# Key-Matrix.net
KiCad netlist of a schematic drawn in Altium Designer
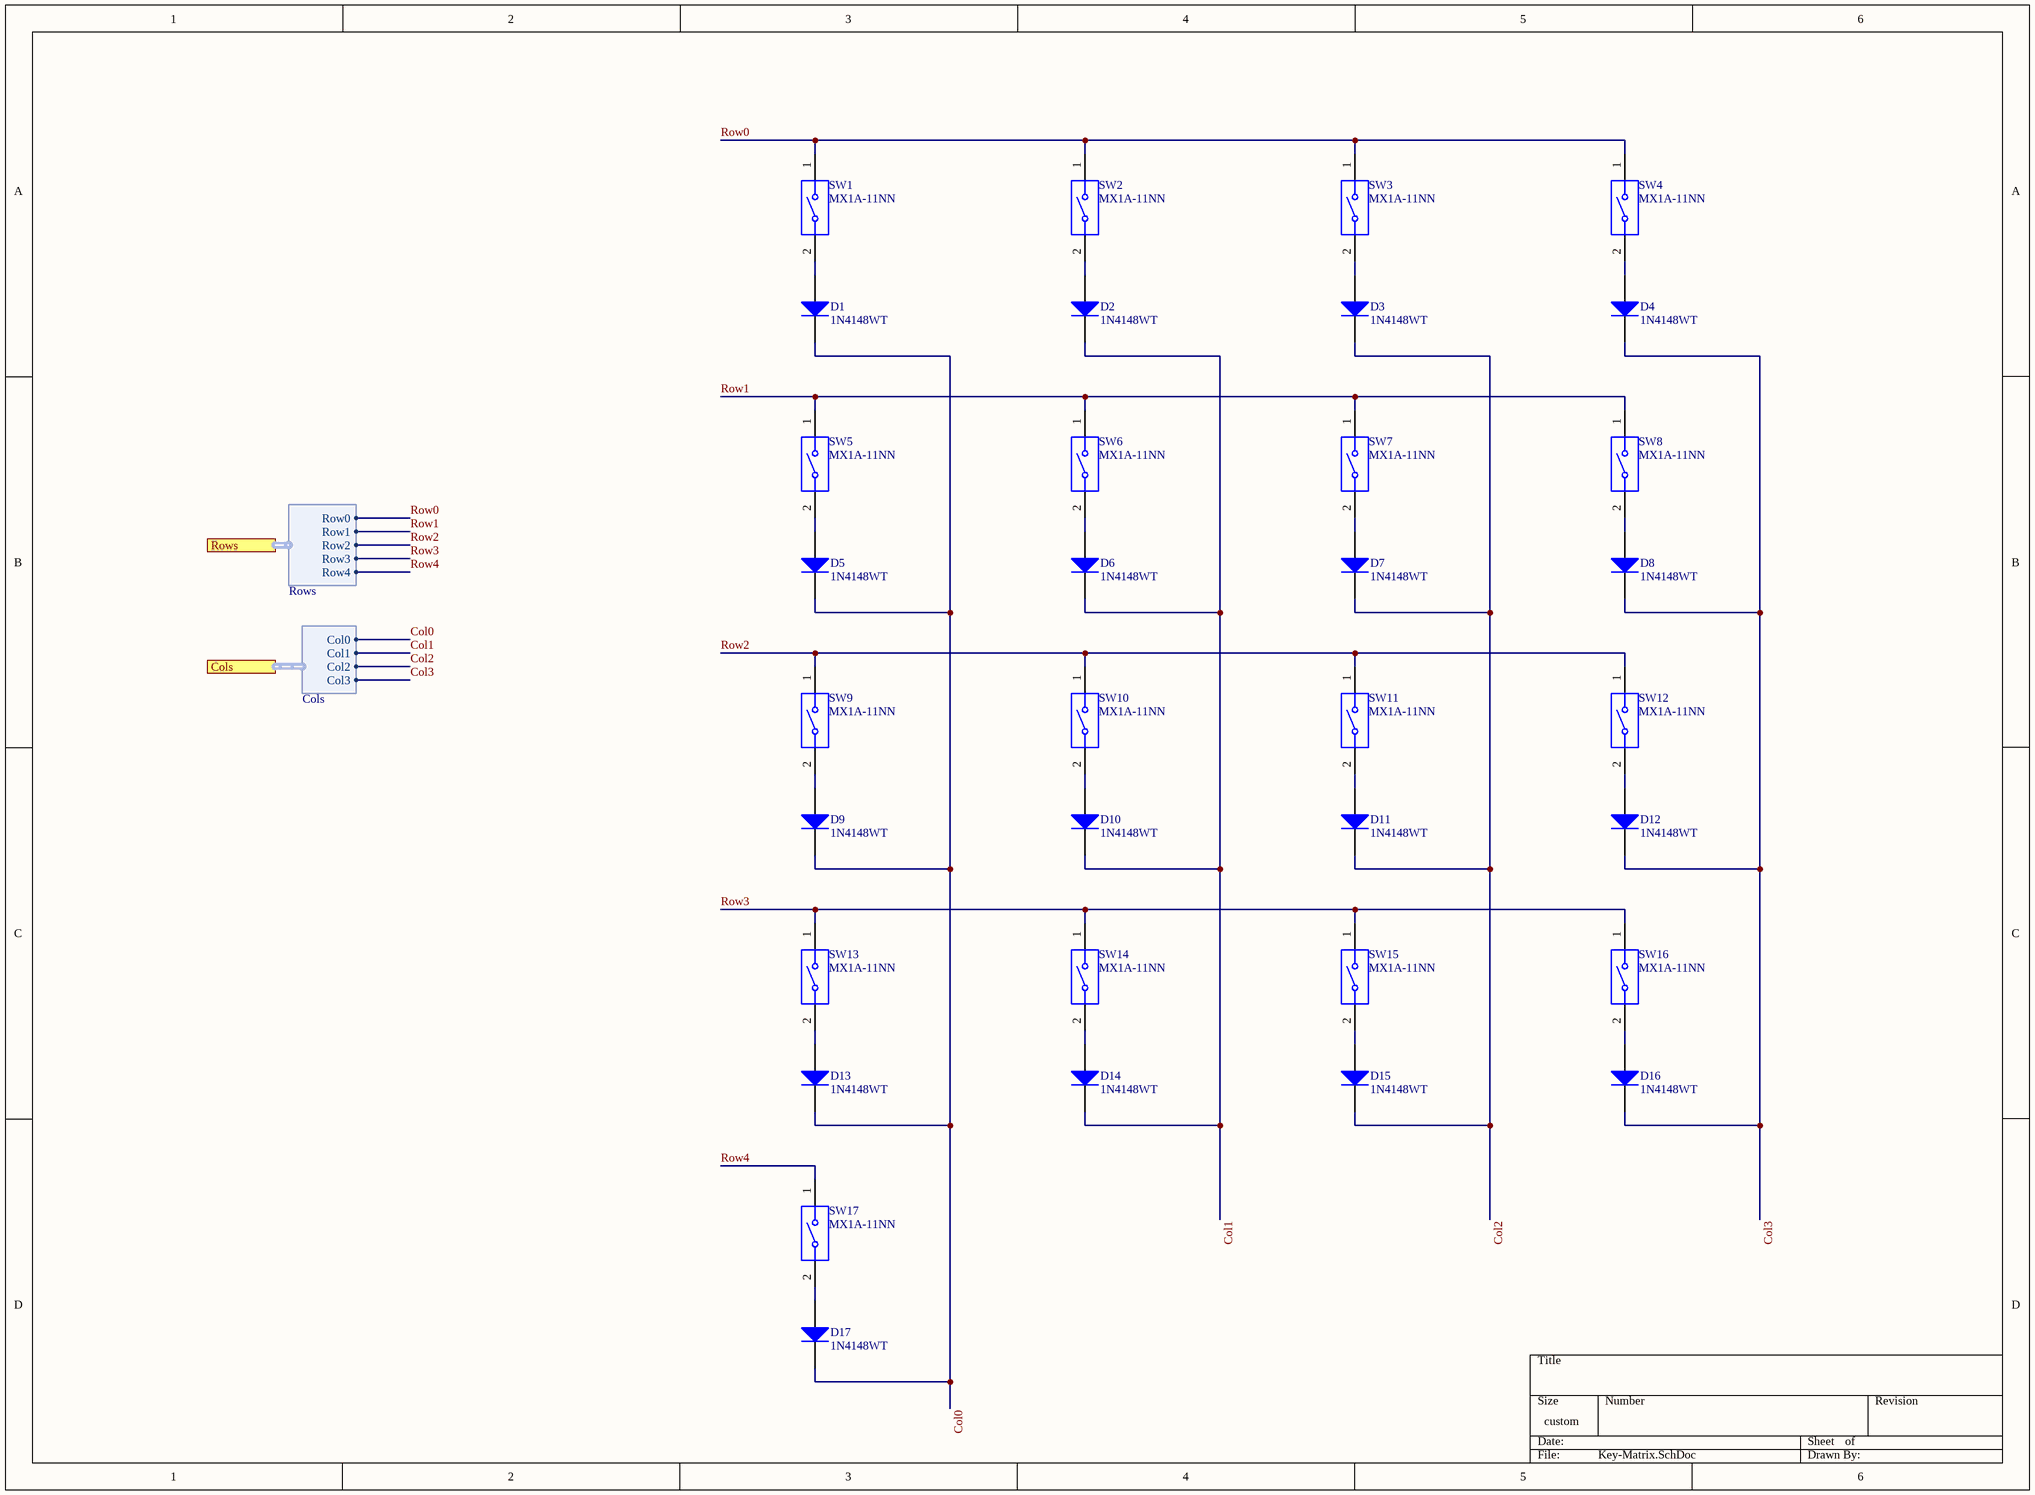
[diagram p0: Key-Matrix.SchDoc]

(export (version "E")
  (design (tool "Eeschema 10.0.6"))
  (components
    (comp (ref "D1")
      (value "1N4148WT")
      (footprint "FAIR-SOD-523F-2_V")
      (description "High Conductance Fast Switching Diode, 75 V, -55 to 150 degC, 2-Pin SOD523F, RoHS")
      (fields (field (name "MANUFACTURER") "Fairchild Semiconductor"))
      (libsource (lib "Altium Content Vault") (part "FAIR-D_K1A2-2"))
    )
    (comp (ref "D2")
      (value "1N4148WT")
      (footprint "FAIR-SOD-523F-2_V")
      (description "High Conductance Fast Switching Diode, 75 V, -55 to 150 degC, 2-Pin SOD523F, RoHS")
      (fields (field (name "MANUFACTURER") "Fairchild Semiconductor"))
      (libsource (lib "Altium Content Vault") (part "FAIR-D_K1A2-2"))
    )
    (comp (ref "D3")
      (value "1N4148WT")
      (footprint "FAIR-SOD-523F-2_V")
      (description "High Conductance Fast Switching Diode, 75 V, -55 to 150 degC, 2-Pin SOD523F, RoHS")
      (fields (field (name "MANUFACTURER") "Fairchild Semiconductor"))
      (libsource (lib "Altium Content Vault") (part "FAIR-D_K1A2-2"))
    )
    (comp (ref "D4")
      (value "1N4148WT")
      (footprint "FAIR-SOD-523F-2_V")
      (description "High Conductance Fast Switching Diode, 75 V, -55 to 150 degC, 2-Pin SOD523F, RoHS")
      (fields (field (name "MANUFACTURER") "Fairchild Semiconductor"))
      (libsource (lib "Altium Content Vault") (part "FAIR-D_K1A2-2"))
    )
    (comp (ref "D5")
      (value "1N4148WT")
      (footprint "FAIR-SOD-523F-2_V")
      (description "High Conductance Fast Switching Diode, 75 V, -55 to 150 degC, 2-Pin SOD523F, RoHS")
      (fields (field (name "MANUFACTURER") "Fairchild Semiconductor"))
      (libsource (lib "Altium Content Vault") (part "FAIR-D_K1A2-2"))
    )
    (comp (ref "D6")
      (value "1N4148WT")
      (footprint "FAIR-SOD-523F-2_V")
      (description "High Conductance Fast Switching Diode, 75 V, -55 to 150 degC, 2-Pin SOD523F, RoHS")
      (fields (field (name "MANUFACTURER") "Fairchild Semiconductor"))
      (libsource (lib "Altium Content Vault") (part "FAIR-D_K1A2-2"))
    )
    (comp (ref "D7")
      (value "1N4148WT")
      (footprint "FAIR-SOD-523F-2_V")
      (description "High Conductance Fast Switching Diode, 75 V, -55 to 150 degC, 2-Pin SOD523F, RoHS")
      (fields (field (name "MANUFACTURER") "Fairchild Semiconductor"))
      (libsource (lib "Altium Content Vault") (part "FAIR-D_K1A2-2"))
    )
    (comp (ref "D8")
      (value "1N4148WT")
      (footprint "FAIR-SOD-523F-2_V")
      (description "High Conductance Fast Switching Diode, 75 V, -55 to 150 degC, 2-Pin SOD523F, RoHS")
      (fields (field (name "MANUFACTURER") "Fairchild Semiconductor"))
      (libsource (lib "Altium Content Vault") (part "FAIR-D_K1A2-2"))
    )
    (comp (ref "D9")
      (value "1N4148WT")
      (footprint "FAIR-SOD-523F-2_V")
      (description "High Conductance Fast Switching Diode, 75 V, -55 to 150 degC, 2-Pin SOD523F, RoHS")
      (fields (field (name "MANUFACTURER") "Fairchild Semiconductor"))
      (libsource (lib "Altium Content Vault") (part "FAIR-D_K1A2-2"))
    )
    (comp (ref "D10")
      (value "1N4148WT")
      (footprint "FAIR-SOD-523F-2_V")
      (description "High Conductance Fast Switching Diode, 75 V, -55 to 150 degC, 2-Pin SOD523F, RoHS")
      (fields (field (name "MANUFACTURER") "Fairchild Semiconductor"))
      (libsource (lib "Altium Content Vault") (part "FAIR-D_K1A2-2"))
    )
    (comp (ref "D11")
      (value "1N4148WT")
      (footprint "FAIR-SOD-523F-2_V")
      (description "High Conductance Fast Switching Diode, 75 V, -55 to 150 degC, 2-Pin SOD523F, RoHS")
      (fields (field (name "MANUFACTURER") "Fairchild Semiconductor"))
      (libsource (lib "Altium Content Vault") (part "FAIR-D_K1A2-2"))
    )
    (comp (ref "D12")
      (value "1N4148WT")
      (footprint "FAIR-SOD-523F-2_V")
      (description "High Conductance Fast Switching Diode, 75 V, -55 to 150 degC, 2-Pin SOD523F, RoHS")
      (fields (field (name "MANUFACTURER") "Fairchild Semiconductor"))
      (libsource (lib "Altium Content Vault") (part "FAIR-D_K1A2-2"))
    )
    (comp (ref "D13")
      (value "1N4148WT")
      (footprint "FAIR-SOD-523F-2_V")
      (description "High Conductance Fast Switching Diode, 75 V, -55 to 150 degC, 2-Pin SOD523F, RoHS")
      (fields (field (name "MANUFACTURER") "Fairchild Semiconductor"))
      (libsource (lib "Altium Content Vault") (part "FAIR-D_K1A2-2"))
    )
    (comp (ref "D14")
      (value "1N4148WT")
      (footprint "FAIR-SOD-523F-2_V")
      (description "High Conductance Fast Switching Diode, 75 V, -55 to 150 degC, 2-Pin SOD523F, RoHS")
      (fields (field (name "MANUFACTURER") "Fairchild Semiconductor"))
      (libsource (lib "Altium Content Vault") (part "FAIR-D_K1A2-2"))
    )
    (comp (ref "D15")
      (value "1N4148WT")
      (footprint "FAIR-SOD-523F-2_V")
      (description "High Conductance Fast Switching Diode, 75 V, -55 to 150 degC, 2-Pin SOD523F, RoHS")
      (fields (field (name "MANUFACTURER") "Fairchild Semiconductor"))
      (libsource (lib "Altium Content Vault") (part "FAIR-D_K1A2-2"))
    )
    (comp (ref "D16")
      (value "1N4148WT")
      (footprint "FAIR-SOD-523F-2_V")
      (description "High Conductance Fast Switching Diode, 75 V, -55 to 150 degC, 2-Pin SOD523F, RoHS")
      (fields (field (name "MANUFACTURER") "Fairchild Semiconductor"))
      (libsource (lib "Altium Content Vault") (part "FAIR-D_K1A2-2"))
    )
    (comp (ref "D17")
      (value "1N4148WT")
      (footprint "FAIR-SOD-523F-2_V")
      (description "High Conductance Fast Switching Diode, 75 V, -55 to 150 degC, 2-Pin SOD523F, RoHS")
      (fields (field (name "MANUFACTURER") "Fairchild Semiconductor"))
      (libsource (lib "Altium Content Vault") (part "FAIR-D_K1A2-2"))
    )
    (comp (ref "SW1")
      (value "MX1A-11NN")
      (footprint "CHRY-MX1A-11NN_V")
      (description "Keymodule MX, SPST, IP40, 12 V Max, 10 mA Max, -10 to 70 degC, 2-Pin THD, RoHS, Bulk")
      (fields (field (name "PART NO") "MX1A11NN") (field (name "MANUFACTURER") "Cherry"))
      (libsource (lib "Altium Content Vault") (part "KEYSW-SPST-2"))
    )
    (comp (ref "SW2")
      (value "MX1A-11NN")
      (footprint "CHRY-MX1A-11NN_V")
      (description "Keymodule MX, SPST, IP40, 12 V Max, 10 mA Max, -10 to 70 degC, 2-Pin THD, RoHS, Bulk")
      (fields (field (name "PART NO") "MX1A11NN") (field (name "MANUFACTURER") "Cherry"))
      (libsource (lib "Altium Content Vault") (part "KEYSW-SPST-2"))
    )
    (comp (ref "SW3")
      (value "MX1A-11NN")
      (footprint "CHRY-MX1A-11NN_V")
      (description "Keymodule MX, SPST, IP40, 12 V Max, 10 mA Max, -10 to 70 degC, 2-Pin THD, RoHS, Bulk")
      (fields (field (name "PART NO") "MX1A11NN") (field (name "MANUFACTURER") "Cherry"))
      (libsource (lib "Altium Content Vault") (part "KEYSW-SPST-2"))
    )
    (comp (ref "SW4")
      (value "MX1A-11NN")
      (footprint "CHRY-MX1A-11NN_V")
      (description "Keymodule MX, SPST, IP40, 12 V Max, 10 mA Max, -10 to 70 degC, 2-Pin THD, RoHS, Bulk")
      (fields (field (name "PART NO") "MX1A11NN") (field (name "MANUFACTURER") "Cherry"))
      (libsource (lib "Altium Content Vault") (part "KEYSW-SPST-2"))
    )
    (comp (ref "SW5")
      (value "MX1A-11NN")
      (footprint "CHRY-MX1A-11NN_V")
      (description "Keymodule MX, SPST, IP40, 12 V Max, 10 mA Max, -10 to 70 degC, 2-Pin THD, RoHS, Bulk")
      (fields (field (name "PART NO") "MX1A11NN") (field (name "MANUFACTURER") "Cherry"))
      (libsource (lib "Altium Content Vault") (part "KEYSW-SPST-2"))
    )
    (comp (ref "SW6")
      (value "MX1A-11NN")
      (footprint "CHRY-MX1A-11NN_V")
      (description "Keymodule MX, SPST, IP40, 12 V Max, 10 mA Max, -10 to 70 degC, 2-Pin THD, RoHS, Bulk")
      (fields (field (name "PART NO") "MX1A11NN") (field (name "MANUFACTURER") "Cherry"))
      (libsource (lib "Altium Content Vault") (part "KEYSW-SPST-2"))
    )
    (comp (ref "SW7")
      (value "MX1A-11NN")
      (footprint "CHRY-MX1A-11NN_V")
      (description "Keymodule MX, SPST, IP40, 12 V Max, 10 mA Max, -10 to 70 degC, 2-Pin THD, RoHS, Bulk")
      (fields (field (name "PART NO") "MX1A11NN") (field (name "MANUFACTURER") "Cherry"))
      (libsource (lib "Altium Content Vault") (part "KEYSW-SPST-2"))
    )
    (comp (ref "SW8")
      (value "MX1A-11NN")
      (footprint "CHRY-MX1A-11NN_V")
      (description "Keymodule MX, SPST, IP40, 12 V Max, 10 mA Max, -10 to 70 degC, 2-Pin THD, RoHS, Bulk")
      (fields (field (name "PART NO") "MX1A11NN") (field (name "MANUFACTURER") "Cherry"))
      (libsource (lib "Altium Content Vault") (part "KEYSW-SPST-2"))
    )
    (comp (ref "SW9")
      (value "MX1A-11NN")
      (footprint "CHRY-MX1A-11NN_V")
      (description "Keymodule MX, SPST, IP40, 12 V Max, 10 mA Max, -10 to 70 degC, 2-Pin THD, RoHS, Bulk")
      (fields (field (name "PART NO") "MX1A11NN") (field (name "MANUFACTURER") "Cherry"))
      (libsource (lib "Altium Content Vault") (part "KEYSW-SPST-2"))
    )
    (comp (ref "SW10")
      (value "MX1A-11NN")
      (footprint "CHRY-MX1A-11NN_V")
      (description "Keymodule MX, SPST, IP40, 12 V Max, 10 mA Max, -10 to 70 degC, 2-Pin THD, RoHS, Bulk")
      (fields (field (name "PART NO") "MX1A11NN") (field (name "MANUFACTURER") "Cherry"))
      (libsource (lib "Altium Content Vault") (part "KEYSW-SPST-2"))
    )
    (comp (ref "SW11")
      (value "MX1A-11NN")
      (footprint "CHRY-MX1A-11NN_V")
      (description "Keymodule MX, SPST, IP40, 12 V Max, 10 mA Max, -10 to 70 degC, 2-Pin THD, RoHS, Bulk")
      (fields (field (name "PART NO") "MX1A11NN") (field (name "MANUFACTURER") "Cherry"))
      (libsource (lib "Altium Content Vault") (part "KEYSW-SPST-2"))
    )
    (comp (ref "SW12")
      (value "MX1A-11NN")
      (footprint "CHRY-MX1A-11NN_V")
      (description "Keymodule MX, SPST, IP40, 12 V Max, 10 mA Max, -10 to 70 degC, 2-Pin THD, RoHS, Bulk")
      (fields (field (name "PART NO") "MX1A11NN") (field (name "MANUFACTURER") "Cherry"))
      (libsource (lib "Altium Content Vault") (part "KEYSW-SPST-2"))
    )
    (comp (ref "SW13")
      (value "MX1A-11NN")
      (footprint "CHRY-MX1A-11NN_V")
      (description "Keymodule MX, SPST, IP40, 12 V Max, 10 mA Max, -10 to 70 degC, 2-Pin THD, RoHS, Bulk")
      (fields (field (name "PART NO") "MX1A11NN") (field (name "MANUFACTURER") "Cherry"))
      (libsource (lib "Altium Content Vault") (part "KEYSW-SPST-2"))
    )
    (comp (ref "SW14")
      (value "MX1A-11NN")
      (footprint "CHRY-MX1A-11NN_V")
      (description "Keymodule MX, SPST, IP40, 12 V Max, 10 mA Max, -10 to 70 degC, 2-Pin THD, RoHS, Bulk")
      (fields (field (name "PART NO") "MX1A11NN") (field (name "MANUFACTURER") "Cherry"))
      (libsource (lib "Altium Content Vault") (part "KEYSW-SPST-2"))
    )
    (comp (ref "SW15")
      (value "MX1A-11NN")
      (footprint "CHRY-MX1A-11NN_V")
      (description "Keymodule MX, SPST, IP40, 12 V Max, 10 mA Max, -10 to 70 degC, 2-Pin THD, RoHS, Bulk")
      (fields (field (name "PART NO") "MX1A11NN") (field (name "MANUFACTURER") "Cherry"))
      (libsource (lib "Altium Content Vault") (part "KEYSW-SPST-2"))
    )
    (comp (ref "SW16")
      (value "MX1A-11NN")
      (footprint "CHRY-MX1A-11NN_V")
      (description "Keymodule MX, SPST, IP40, 12 V Max, 10 mA Max, -10 to 70 degC, 2-Pin THD, RoHS, Bulk")
      (fields (field (name "PART NO") "MX1A11NN") (field (name "MANUFACTURER") "Cherry"))
      (libsource (lib "Altium Content Vault") (part "KEYSW-SPST-2"))
    )
    (comp (ref "SW17")
      (value "MX1A-11NN")
      (footprint "CHRY-MX1A-11NN_V")
      (description "Keymodule MX, SPST, IP40, 12 V Max, 10 mA Max, -10 to 70 degC, 2-Pin THD, RoHS, Bulk")
      (fields (field (name "PART NO") "MX1A11NN") (field (name "MANUFACTURER") "Cherry"))
      (libsource (lib "Altium Content Vault") (part "KEYSW-SPST-2"))
    )
  )
  (nets
    (net (code "3") (name "/Col0") (class "Default")
      (node (ref "D1") (pin "1") (pinfunction "K_1") (pintype "passive"))
      (node (ref "D13") (pin "1") (pinfunction "K_1") (pintype "passive"))
      (node (ref "D17") (pin "1") (pinfunction "K_1") (pintype "passive"))
      (node (ref "D5") (pin "1") (pinfunction "K_1") (pintype "passive"))
      (node (ref "D9") (pin "1") (pinfunction "K_1") (pintype "passive"))
    )
    (net (code "4") (name "/Col1") (class "Default")
      (node (ref "D10") (pin "1") (pinfunction "K_1") (pintype "passive"))
      (node (ref "D14") (pin "1") (pinfunction "K_1") (pintype "passive"))
      (node (ref "D2") (pin "1") (pinfunction "K_1") (pintype "passive"))
      (node (ref "D6") (pin "1") (pinfunction "K_1") (pintype "passive"))
    )
    (net (code "5") (name "/Col2") (class "Default")
      (node (ref "D11") (pin "1") (pinfunction "K_1") (pintype "passive"))
      (node (ref "D15") (pin "1") (pinfunction "K_1") (pintype "passive"))
      (node (ref "D3") (pin "1") (pinfunction "K_1") (pintype "passive"))
      (node (ref "D7") (pin "1") (pinfunction "K_1") (pintype "passive"))
    )
    (net (code "6") (name "/Col3") (class "Default")
      (node (ref "D12") (pin "1") (pinfunction "K_1") (pintype "passive"))
      (node (ref "D16") (pin "1") (pinfunction "K_1") (pintype "passive"))
      (node (ref "D4") (pin "1") (pinfunction "K_1") (pintype "passive"))
      (node (ref "D8") (pin "1") (pinfunction "K_1") (pintype "passive"))
    )
    (net (code "7") (name "/Row0") (class "Default")
      (node (ref "SW1") (pin "1") (pinfunction "1_1") (pintype "passive"))
      (node (ref "SW2") (pin "1") (pinfunction "1_1") (pintype "passive"))
      (node (ref "SW3") (pin "1") (pinfunction "1_1") (pintype "passive"))
      (node (ref "SW4") (pin "1") (pinfunction "1_1") (pintype "passive"))
    )
    (net (code "8") (name "/Row1") (class "Default")
      (node (ref "SW5") (pin "1") (pinfunction "1_1") (pintype "passive"))
      (node (ref "SW6") (pin "1") (pinfunction "1_1") (pintype "passive"))
      (node (ref "SW7") (pin "1") (pinfunction "1_1") (pintype "passive"))
      (node (ref "SW8") (pin "1") (pinfunction "1_1") (pintype "passive"))
    )
    (net (code "9") (name "/Row2") (class "Default")
      (node (ref "SW10") (pin "1") (pinfunction "1_1") (pintype "passive"))
      (node (ref "SW11") (pin "1") (pinfunction "1_1") (pintype "passive"))
      (node (ref "SW12") (pin "1") (pinfunction "1_1") (pintype "passive"))
      (node (ref "SW9") (pin "1") (pinfunction "1_1") (pintype "passive"))
    )
    (net (code "10") (name "/Row3") (class "Default")
      (node (ref "SW13") (pin "1") (pinfunction "1_1") (pintype "passive"))
      (node (ref "SW14") (pin "1") (pinfunction "1_1") (pintype "passive"))
      (node (ref "SW15") (pin "1") (pinfunction "1_1") (pintype "passive"))
      (node (ref "SW16") (pin "1") (pinfunction "1_1") (pintype "passive"))
    )
    (net (code "11") (name "/Row4") (class "Default")
      (node (ref "SW17") (pin "1") (pinfunction "1_1") (pintype "passive"))
    )
    (net (code "14") (name "Net-(D1-A)") (class "Default")
      (node (ref "D1") (pin "2") (pinfunction "A_2") (pintype "passive"))
      (node (ref "SW1") (pin "2") (pinfunction "2_2") (pintype "passive"))
    )
    (net (code "15") (name "Net-(D2-A)") (class "Default")
      (node (ref "D2") (pin "2") (pinfunction "A_2") (pintype "passive"))
      (node (ref "SW2") (pin "2") (pinfunction "2_2") (pintype "passive"))
    )
    (net (code "16") (name "Net-(D3-A)") (class "Default")
      (node (ref "D3") (pin "2") (pinfunction "A_2") (pintype "passive"))
      (node (ref "SW3") (pin "2") (pinfunction "2_2") (pintype "passive"))
    )
    (net (code "17") (name "Net-(D4-A)") (class "Default")
      (node (ref "D4") (pin "2") (pinfunction "A_2") (pintype "passive"))
      (node (ref "SW4") (pin "2") (pinfunction "2_2") (pintype "passive"))
    )
    (net (code "18") (name "Net-(D5-A)") (class "Default")
      (node (ref "D5") (pin "2") (pinfunction "A_2") (pintype "passive"))
      (node (ref "SW5") (pin "2") (pinfunction "2_2") (pintype "passive"))
    )
    (net (code "19") (name "Net-(D6-A)") (class "Default")
      (node (ref "D6") (pin "2") (pinfunction "A_2") (pintype "passive"))
      (node (ref "SW6") (pin "2") (pinfunction "2_2") (pintype "passive"))
    )
    (net (code "20") (name "Net-(D7-A)") (class "Default")
      (node (ref "D7") (pin "2") (pinfunction "A_2") (pintype "passive"))
      (node (ref "SW7") (pin "2") (pinfunction "2_2") (pintype "passive"))
    )
    (net (code "21") (name "Net-(D8-A)") (class "Default")
      (node (ref "D8") (pin "2") (pinfunction "A_2") (pintype "passive"))
      (node (ref "SW8") (pin "2") (pinfunction "2_2") (pintype "passive"))
    )
    (net (code "22") (name "Net-(D9-A)") (class "Default")
      (node (ref "D9") (pin "2") (pinfunction "A_2") (pintype "passive"))
      (node (ref "SW9") (pin "2") (pinfunction "2_2") (pintype "passive"))
    )
    (net (code "23") (name "Net-(D10-A)") (class "Default")
      (node (ref "D10") (pin "2") (pinfunction "A_2") (pintype "passive"))
      (node (ref "SW10") (pin "2") (pinfunction "2_2") (pintype "passive"))
    )
    (net (code "24") (name "Net-(D11-A)") (class "Default")
      (node (ref "D11") (pin "2") (pinfunction "A_2") (pintype "passive"))
      (node (ref "SW11") (pin "2") (pinfunction "2_2") (pintype "passive"))
    )
    (net (code "25") (name "Net-(D12-A)") (class "Default")
      (node (ref "D12") (pin "2") (pinfunction "A_2") (pintype "passive"))
      (node (ref "SW12") (pin "2") (pinfunction "2_2") (pintype "passive"))
    )
    (net (code "26") (name "Net-(D13-A)") (class "Default")
      (node (ref "D13") (pin "2") (pinfunction "A_2") (pintype "passive"))
      (node (ref "SW13") (pin "2") (pinfunction "2_2") (pintype "passive"))
    )
    (net (code "27") (name "Net-(D14-A)") (class "Default")
      (node (ref "D14") (pin "2") (pinfunction "A_2") (pintype "passive"))
      (node (ref "SW14") (pin "2") (pinfunction "2_2") (pintype "passive"))
    )
    (net (code "28") (name "Net-(D15-A)") (class "Default")
      (node (ref "D15") (pin "2") (pinfunction "A_2") (pintype "passive"))
      (node (ref "SW15") (pin "2") (pinfunction "2_2") (pintype "passive"))
    )
    (net (code "29") (name "Net-(D16-A)") (class "Default")
      (node (ref "D16") (pin "2") (pinfunction "A_2") (pintype "passive"))
      (node (ref "SW16") (pin "2") (pinfunction "2_2") (pintype "passive"))
    )
    (net (code "30") (name "Net-(D17-A)") (class "Default")
      (node (ref "D17") (pin "2") (pinfunction "A_2") (pintype "passive"))
      (node (ref "SW17") (pin "2") (pinfunction "2_2") (pintype "passive"))
    )
  )
)
